# reciever.net
KiCad netlist of a schematic drawn in EAGLE
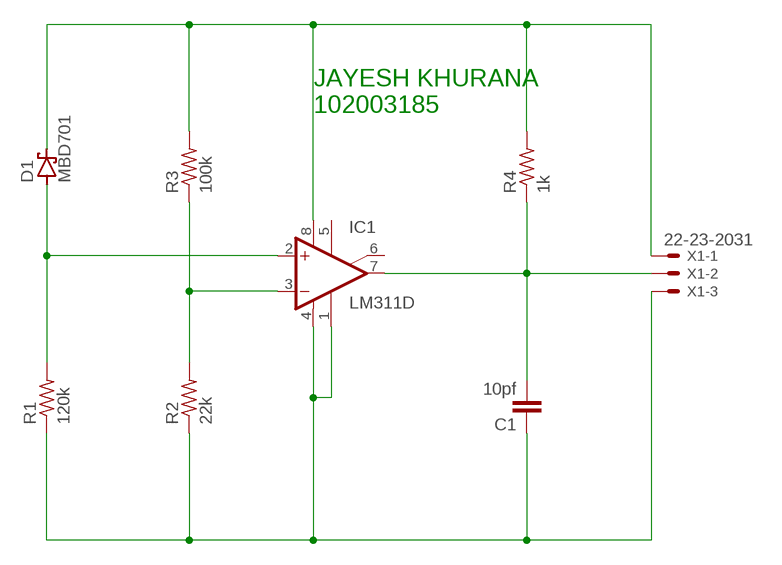
[diagram p0: schematic, sheet 1]

(export (version "E")
  (design (tool "Eeschema 10.0.6"))
  (components
    (comp (ref "C1")
      (value "10pf")
      (footprint "eagle-import:C2.5-2")
      (libsource (lib "eagle-import") (part "C2.5/2"))
    )
    (comp (ref "D1")
      (value "MBD701")
      (footprint "eagle-import:TO92H")
      (libsource (lib "eagle-import") (part "MBD701"))
    )
    (comp (ref "IC1")
      (value "LM311D")
      (footprint "eagle-import:SO08")
      (libsource (lib "eagle-import") (part "LM311D"))
    )
    (comp (ref "R1")
      (value "120k")
      (footprint "eagle-import:0207_10")
      (libsource (lib "eagle-import") (part "R-US_0207/10"))
    )
    (comp (ref "R2")
      (value "22k")
      (footprint "eagle-import:0207_10")
      (libsource (lib "eagle-import") (part "R-US_0207/10"))
    )
    (comp (ref "R3")
      (value "100k")
      (footprint "eagle-import:0207_10")
      (libsource (lib "eagle-import") (part "R-US_0207/10"))
    )
    (comp (ref "R4")
      (value "1k")
      (footprint "eagle-import:0207_10")
      (libsource (lib "eagle-import") (part "R-US_0207/10"))
    )
    (comp (ref "X1")
      (value "22-23-2031")
      (footprint "eagle-import:22-23-2031")
      (fields (field (name "MF") "MOLEX"))
      (libsource (lib "eagle-import") (part "22-23-2031"))
    )
  )
  (nets
    (net (code "1") (name "Net-(D1-A)") (class "Default")
      (node (ref "D1") (pin "1") (pinfunction "A_1") (pintype "passive"))
      (node (ref "IC1") (pin "2") (pinfunction "+IN_2") (pintype "input"))
      (node (ref "R1") (pin "2") (pinfunction "2_2") (pintype "passive"))
    )
    (net (code "2") (name "Net-(D1-C)") (class "Default")
      (node (ref "D1") (pin "2") (pinfunction "C_2") (pintype "passive"))
      (node (ref "IC1") (pin "8") (pinfunction "V+_8") (pintype "power_in"))
      (node (ref "R3") (pin "2") (pinfunction "2_2") (pintype "passive"))
      (node (ref "R4") (pin "2") (pinfunction "2_2") (pintype "passive"))
      (node (ref "X1") (pin "1") (pinfunction "S_1") (pintype "passive"))
    )
    (net (code "3") (name "Net-(IC1--IN)") (class "Default")
      (node (ref "IC1") (pin "3") (pinfunction "-IN_3") (pintype "input"))
      (node (ref "R2") (pin "2") (pinfunction "2_2") (pintype "passive"))
      (node (ref "R3") (pin "1") (pinfunction "1_1") (pintype "passive"))
    )
    (net (code "4") (name "Net-(IC1-GND)") (class "Default")
      (node (ref "C1") (pin "1") (pinfunction "1_1") (pintype "passive"))
      (node (ref "IC1") (pin "1") (pinfunction "GND_1") (pintype "passive"))
      (node (ref "IC1") (pin "4") (pinfunction "V-_4") (pintype "power_in"))
      (node (ref "R1") (pin "1") (pinfunction "1_1") (pintype "passive"))
      (node (ref "R2") (pin "1") (pinfunction "1_1") (pintype "passive"))
      (node (ref "X1") (pin "3") (pinfunction "S_3") (pintype "passive"))
    )
    (net (code "5") (name "Net-(IC1-OUT)") (class "Default")
      (node (ref "C1") (pin "2") (pinfunction "2_2") (pintype "passive"))
      (node (ref "IC1") (pin "7") (pinfunction "OUT_7") (pintype "output"))
      (node (ref "R4") (pin "1") (pinfunction "1_1") (pintype "passive"))
      (node (ref "X1") (pin "2") (pinfunction "S_2") (pintype "passive"))
    )
    (net (code "6") (name "unconnected-(IC1-ON-Pad5)") (class "Default")
      (node (ref "IC1") (pin "5") (pinfunction "ON_5") (pintype "passive"))
    )
    (net (code "7") (name "unconnected-(IC1-ON{slash}STR-Pad6)") (class "Default")
      (node (ref "IC1") (pin "6") (pinfunction "ON/STR_6") (pintype "passive"))
    )
  )
)
